# controller.net
KiCad netlist of a schematic drawn in EAGLE
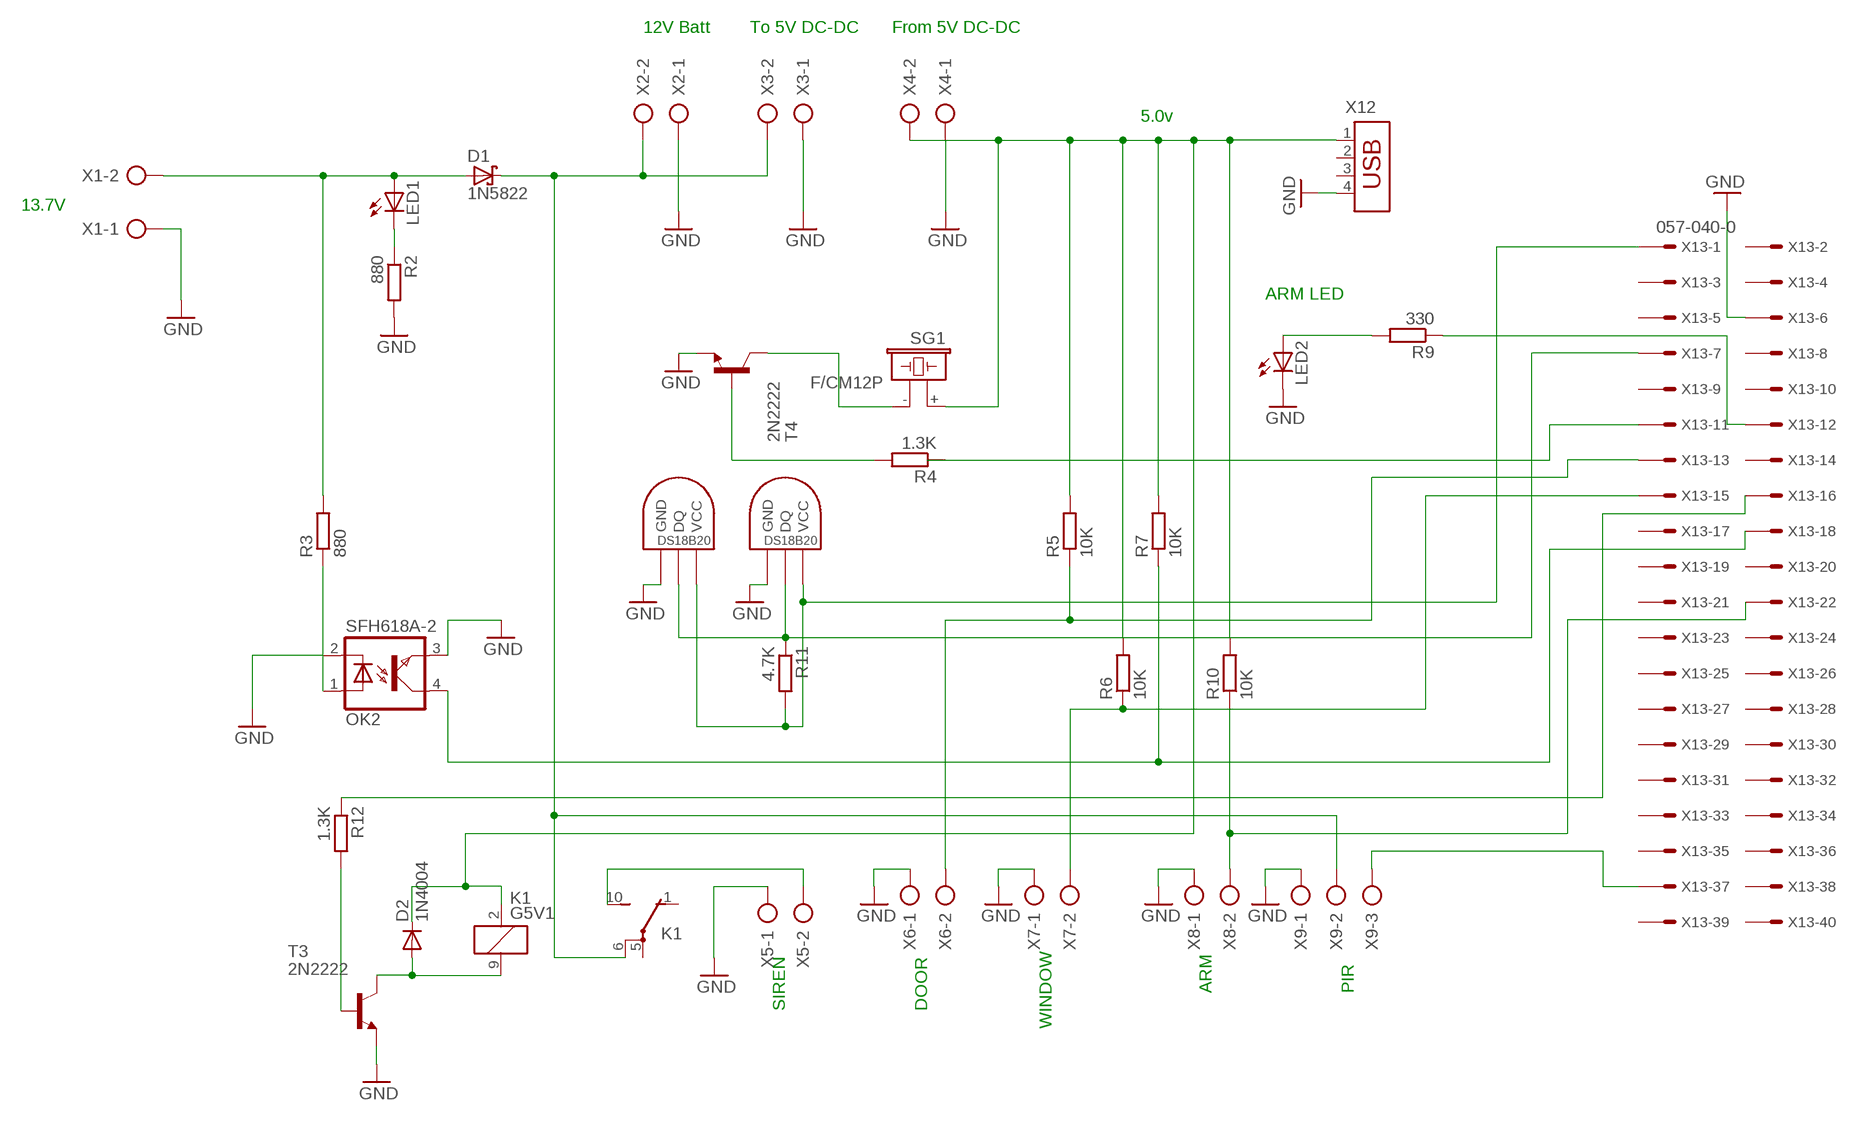
[diagram p0: schematic, sheet 1]

(export (version "E")
  (design (tool "Eeschema 10.0.6"))
  (components
    (comp (ref "D1")
      (value "1N5822")
      (footprint "eagle-import:DO201T15")
      (libsource (lib "eagle-import") (part "SCHOTTKY-DIODEDO201T15"))
    )
    (comp (ref "D2")
      (value "1N4004")
      (footprint "eagle-import:DO41-10")
      (libsource (lib "eagle-import") (part "1N4004"))
    )
    (comp (ref "K1")
      (value "G5V1")
      (footprint "eagle-import:G5V1")
      (fields (field (name "MPN") "G5V-1-DC24"))
      (libsource (lib "eagle-import") (part "G5V1"))
    )
    (comp (ref "LED1")
      (value "LED5MM")
      (footprint "eagle-import:LED5MM")
      (libsource (lib "eagle-import") (part "LED5MM"))
    )
    (comp (ref "LED2")
      (value "LED5MM")
      (footprint "eagle-import:LED5MM")
      (libsource (lib "eagle-import") (part "LED5MM"))
    )
    (comp (ref "OK2")
      (value "SFH618A-2")
      (footprint "eagle-import:DIP4")
      (fields (field (name "MF") "VISHAY/TELEFUNKEN"))
      (libsource (lib "eagle-import") (part "SFH618?A-2"))
    )
    (comp (ref "R2")
      (value "880")
      (footprint "eagle-import:0204_7")
      (libsource (lib "eagle-import") (part "R-EU_0204/7"))
    )
    (comp (ref "R3")
      (value "880")
      (footprint "eagle-import:0204_7")
      (libsource (lib "eagle-import") (part "R-EU_0204/7"))
    )
    (comp (ref "R4")
      (value "1.3K")
      (footprint "eagle-import:0204_7")
      (libsource (lib "eagle-import") (part "R-EU_0204/7"))
    )
    (comp (ref "R5")
      (value "10K")
      (footprint "eagle-import:0204_7")
      (libsource (lib "eagle-import") (part "R-EU_0204/7"))
    )
    (comp (ref "R6")
      (value "10K")
      (footprint "eagle-import:0204_7")
      (libsource (lib "eagle-import") (part "R-EU_0204/7"))
    )
    (comp (ref "R7")
      (value "10K")
      (footprint "eagle-import:0204_7")
      (libsource (lib "eagle-import") (part "R-EU_0204/7"))
    )
    (comp (ref "R9")
      (value "330")
      (footprint "eagle-import:0204_7")
      (libsource (lib "eagle-import") (part "R-EU_0204/7"))
    )
    (comp (ref "R10")
      (value "10K")
      (footprint "eagle-import:0204_7")
      (libsource (lib "eagle-import") (part "R-EU_0204/7"))
    )
    (comp (ref "R11")
      (value "4.7K")
      (footprint "eagle-import:0204_7")
      (libsource (lib "eagle-import") (part "R-EU_0204/7"))
    )
    (comp (ref "R12")
      (value "1.3K")
      (footprint "eagle-import:0204_7")
      (libsource (lib "eagle-import") (part "R-EU_0204/7"))
    )
    (comp (ref "SG1")
      (value "F/CM12P")
      (footprint "eagle-import:F_CM12P")
      (libsource (lib "eagle-import") (part "F/CM12P"))
    )
    (comp (ref "T3")
      (value "2N2222")
      (footprint "eagle-import:TO92-EBC")
      (libsource (lib "eagle-import") (part "-NPN-TO92-EBC2N2222"))
    )
    (comp (ref "T4")
      (value "2N2222")
      (footprint "eagle-import:TO92-EBC")
      (libsource (lib "eagle-import") (part "-NPN-TO92-EBC2N2222"))
    )
    (comp (ref "U$1")
      (value "DS1820TO92")
      (footprint "eagle-import:DS1820")
      (libsource (lib "eagle-import") (part "DS1820TO92"))
    )
    (comp (ref "U$2")
      (value "DS1820TO92")
      (footprint "eagle-import:DS1820")
      (libsource (lib "eagle-import") (part "DS1820TO92"))
    )
    (comp (ref "X1")
      (value "AK500/2")
      (footprint "eagle-import:AK500_2")
      (libsource (lib "eagle-import") (part "AK500/2"))
    )
    (comp (ref "X2")
      (value "AK500/2")
      (footprint "eagle-import:AK500_2")
      (libsource (lib "eagle-import") (part "AK500/2"))
    )
    (comp (ref "X3")
      (value "AK500/2")
      (footprint "eagle-import:AK500_2")
      (libsource (lib "eagle-import") (part "AK500/2"))
    )
    (comp (ref "X4")
      (value "AK500/2")
      (footprint "eagle-import:AK500_2")
      (libsource (lib "eagle-import") (part "AK500/2"))
    )
    (comp (ref "X5")
      (value "AK500/2")
      (footprint "eagle-import:AK500_2")
      (libsource (lib "eagle-import") (part "AK500/2"))
    )
    (comp (ref "X6")
      (value "AK500/2")
      (footprint "eagle-import:AK500_2")
      (libsource (lib "eagle-import") (part "AK500/2"))
    )
    (comp (ref "X7")
      (value "AK500/2")
      (footprint "eagle-import:AK500_2")
      (libsource (lib "eagle-import") (part "AK500/2"))
    )
    (comp (ref "X8")
      (value "AK500/2")
      (footprint "eagle-import:AK500_2")
      (libsource (lib "eagle-import") (part "AK500/2"))
    )
    (comp (ref "X9")
      (value "AK500/3-H")
      (footprint "eagle-import:AK500_3-H")
      (libsource (lib "eagle-import") (part "AK500/3-H"))
    )
    (comp (ref "X12")
      (value "USB-787616")
      (footprint "eagle-import:USB")
      (libsource (lib "eagle-import") (part "USB-787616"))
    )
    (comp (ref "X13")
      (value "057-040-0")
      (footprint "eagle-import:057-040-0")
      (libsource (lib "eagle-import") (part "057-040-0"))
    )
  )
  (nets
    (net (code "1") (name "GND") (class "Default")
      (node (ref "LED2") (pin "K") (pinfunction "C_K") (pintype "passive"))
      (node (ref "OK2") (pin "2") (pinfunction "C_2") (pintype "passive"))
      (node (ref "OK2") (pin "3") (pinfunction "EMIT_3") (pintype "passive"))
      (node (ref "R2") (pin "2") (pinfunction "2_2") (pintype "passive"))
      (node (ref "T3") (pin "E") (pinfunction "E_E") (pintype "passive"))
      (node (ref "T4") (pin "E") (pinfunction "E_E") (pintype "passive"))
      (node (ref "U$1") (pin "GND") (pinfunction "GND_GND") (pintype "power_in"))
      (node (ref "U$2") (pin "GND") (pinfunction "GND_GND") (pintype "power_in"))
      (node (ref "X1") (pin "1") (pinfunction "KL_1") (pintype "passive"))
      (node (ref "X12") (pin "4") (pinfunction "4_4") (pintype "passive"))
      (node (ref "X13") (pin "6") (pinfunction "S_6") (pintype "passive"))
      (node (ref "X2") (pin "1") (pinfunction "KL_1") (pintype "passive"))
      (node (ref "X3") (pin "1") (pinfunction "KL_1") (pintype "passive"))
      (node (ref "X4") (pin "1") (pinfunction "KL_1") (pintype "passive"))
      (node (ref "X5") (pin "1") (pinfunction "KL_1") (pintype "passive"))
      (node (ref "X6") (pin "1") (pinfunction "KL_1") (pintype "passive"))
      (node (ref "X7") (pin "1") (pinfunction "KL_1") (pintype "passive"))
      (node (ref "X8") (pin "1") (pinfunction "KL_1") (pintype "passive"))
      (node (ref "X9") (pin "1") (pinfunction "KL_1") (pintype "passive"))
    )
    (net (code "2") (name "Net-(K1A-1)") (class "Default")
      (node (ref "D2") (pin "C") (pinfunction "C_C") (pintype "passive"))
      (node (ref "K1") (pin "2") (pinfunction "1_2") (pintype "passive"))
      (node (ref "R10") (pin "2") (pinfunction "2_2") (pintype "passive"))
      (node (ref "R5") (pin "2") (pinfunction "2_2") (pintype "passive"))
      (node (ref "R6") (pin "2") (pinfunction "2_2") (pintype "passive"))
      (node (ref "R7") (pin "2") (pinfunction "2_2") (pintype "passive"))
      (node (ref "SG1") (pin "+") (pinfunction "1_+") (pintype "passive"))
      (node (ref "X12") (pin "1") (pinfunction "1_1") (pintype "passive"))
      (node (ref "X4") (pin "2") (pinfunction "KL_2") (pintype "passive"))
    )
    (net (code "3") (name "Net-(K1A-2)") (class "Default")
      (node (ref "D2") (pin "A") (pinfunction "A_A") (pintype "passive"))
      (node (ref "K1") (pin "9") (pinfunction "2_9") (pintype "passive"))
      (node (ref "T3") (pin "C") (pinfunction "C_C") (pintype "passive"))
    )
    (net (code "4") (name "Net-(K1B-S)") (class "Default")
      (node (ref "K1") (pin "10") (pinfunction "S_10") (pintype "passive"))
      (node (ref "X5") (pin "2") (pinfunction "KL_2") (pintype "passive"))
    )
    (net (code "5") (name "Net-(LED1-C)") (class "Default")
      (node (ref "LED1") (pin "K") (pinfunction "C_K") (pintype "passive"))
      (node (ref "R2") (pin "1") (pinfunction "1_1") (pintype "passive"))
    )
    (net (code "6") (name "Net-(LED2-PadA)") (class "Default")
      (node (ref "LED2") (pin "A") (pinfunction "A_A") (pintype "passive"))
      (node (ref "R9") (pin "2") (pinfunction "2_2") (pintype "passive"))
    )
    (net (code "7") (name "Net-(OK2-A)") (class "Default")
      (node (ref "OK2") (pin "1") (pinfunction "A_1") (pintype "passive"))
      (node (ref "R3") (pin "1") (pinfunction "1_1") (pintype "passive"))
    )
    (net (code "8") (name "Net-(OK2-COL)") (class "Default")
      (node (ref "OK2") (pin "4") (pinfunction "COL_4") (pintype "passive"))
      (node (ref "R7") (pin "1") (pinfunction "1_1") (pintype "passive"))
      (node (ref "X13") (pin "18") (pinfunction "S_18") (pintype "passive"))
    )
    (net (code "9") (name "Net-(R4-Pad2)") (class "Default")
      (node (ref "R4") (pin "2") (pinfunction "2_2") (pintype "passive"))
      (node (ref "T4") (pin "B") (pinfunction "B_B") (pintype "passive"))
    )
    (net (code "10") (name "Net-(R12-Pad2)") (class "Default")
      (node (ref "R12") (pin "2") (pinfunction "2_2") (pintype "passive"))
      (node (ref "T3") (pin "B") (pinfunction "B_B") (pintype "passive"))
    )
    (net (code "11") (name "Net-(SG1-2)") (class "Default")
      (node (ref "SG1") (pin "-") (pinfunction "2_-") (pintype "passive"))
      (node (ref "T4") (pin "C") (pinfunction "C_C") (pintype "passive"))
    )
    (net (code "12") (name "Net-(U$1-VCC)") (class "Default")
      (node (ref "R11") (pin "2") (pinfunction "2_2") (pintype "passive"))
      (node (ref "U$1") (pin "VDD") (pinfunction "VCC_VDD") (pintype "power_in"))
      (node (ref "U$2") (pin "VDD") (pinfunction "VCC_VDD") (pintype "power_in"))
      (node (ref "X13") (pin "1") (pinfunction "S_1") (pintype "passive"))
    )
    (net (code "13") (name "Net-(X1B-KL)") (class "Default")
      (node (ref "D1") (pin "A") (pinfunction "A_A") (pintype "passive"))
      (node (ref "LED1") (pin "A") (pinfunction "A_A") (pintype "passive"))
      (node (ref "R3") (pin "2") (pinfunction "2_2") (pintype "passive"))
      (node (ref "X1") (pin "2") (pinfunction "KL_2") (pintype "passive"))
    )
    (net (code "14") (name "Net-(X2B-KL)") (class "Default")
      (node (ref "D1") (pin "C") (pinfunction "C_C") (pintype "passive"))
      (node (ref "K1") (pin "6") (pinfunction "P_6") (pintype "passive"))
      (node (ref "X2") (pin "2") (pinfunction "KL_2") (pintype "passive"))
      (node (ref "X3") (pin "2") (pinfunction "KL_2") (pintype "passive"))
      (node (ref "X9") (pin "2") (pinfunction "KL_2") (pintype "passive"))
    )
    (net (code "15") (name "Net-(X13AE-S)") (class "Default")
      (node (ref "X13") (pin "37") (pinfunction "S_37") (pintype "passive"))
      (node (ref "X9") (pin "3") (pinfunction "KL_3") (pintype "passive"))
    )
    (net (code "16") (name "Net-(X13AL-S)") (class "Default")
      (node (ref "R11") (pin "1") (pinfunction "1_1") (pintype "passive"))
      (node (ref "U$1") (pin "DQ") (pinfunction "DQ_DQ") (pintype "bidirectional"))
      (node (ref "U$2") (pin "DQ") (pinfunction "DQ_DQ") (pintype "bidirectional"))
      (node (ref "X13") (pin "7") (pinfunction "S_7") (pintype "passive"))
    )
    (net (code "17") (name "Net-(X13C-S)") (class "Default")
      (node (ref "R4") (pin "1") (pinfunction "1_1") (pintype "passive"))
      (node (ref "X13") (pin "11") (pinfunction "S_11") (pintype "passive"))
    )
    (net (code "18") (name "Net-(X13D-S)") (class "Default")
      (node (ref "R9") (pin "1") (pinfunction "1_1") (pintype "passive"))
      (node (ref "X13") (pin "12") (pinfunction "S_12") (pintype "passive"))
    )
    (net (code "19") (name "Net-(X13E-S)") (class "Default")
      (node (ref "R5") (pin "1") (pinfunction "1_1") (pintype "passive"))
      (node (ref "X13") (pin "13") (pinfunction "S_13") (pintype "passive"))
      (node (ref "X6") (pin "2") (pinfunction "KL_2") (pintype "passive"))
    )
    (net (code "20") (name "Net-(X13G-S)") (class "Default")
      (node (ref "R6") (pin "1") (pinfunction "1_1") (pintype "passive"))
      (node (ref "X13") (pin "15") (pinfunction "S_15") (pintype "passive"))
      (node (ref "X7") (pin "2") (pinfunction "KL_2") (pintype "passive"))
    )
    (net (code "21") (name "Net-(X13H-S)") (class "Default")
      (node (ref "R12") (pin "1") (pinfunction "1_1") (pintype "passive"))
      (node (ref "X13") (pin "16") (pinfunction "S_16") (pintype "passive"))
    )
    (net (code "22") (name "Net-(X13O-S)") (class "Default")
      (node (ref "R10") (pin "1") (pinfunction "1_1") (pintype "passive"))
      (node (ref "X13") (pin "22") (pinfunction "S_22") (pintype "passive"))
      (node (ref "X8") (pin "2") (pinfunction "KL_2") (pintype "passive"))
    )
    (net (code "23") (name "unconnected-(K1B-O-Pad1)") (class "Default")
      (node (ref "K1") (pin "1") (pinfunction "O_1") (pintype "passive"))
    )
    (net (code "24") (name "unconnected-(K1B-P-Pad5)") (class "Default")
      (node (ref "K1") (pin "5") (pinfunction "P_5") (pintype "passive"))
    )
    (net (code "25") (name "unconnected-(X12-Pad2)") (class "Default")
      (node (ref "X12") (pin "2") (pinfunction "2_2") (pintype "passive"))
    )
    (net (code "26") (name "unconnected-(X12-Pad3)") (class "Default")
      (node (ref "X12") (pin "3") (pinfunction "3_3") (pintype "passive"))
    )
    (net (code "27") (name "unconnected-(X13AA-S-Pad33)") (class "Default")
      (node (ref "X13") (pin "33") (pinfunction "S_33") (pintype "passive"))
    )
    (net (code "28") (name "unconnected-(X13AB-S-Pad34)") (class "Default")
      (node (ref "X13") (pin "34") (pinfunction "S_34") (pintype "passive"))
    )
    (net (code "29") (name "unconnected-(X13AC-S-Pad35)") (class "Default")
      (node (ref "X13") (pin "35") (pinfunction "S_35") (pintype "passive"))
    )
    (net (code "30") (name "unconnected-(X13AD-S-Pad36)") (class "Default")
      (node (ref "X13") (pin "36") (pinfunction "S_36") (pintype "passive"))
    )
    (net (code "31") (name "unconnected-(X13AF-S-Pad38)") (class "Default")
      (node (ref "X13") (pin "38") (pinfunction "S_38") (pintype "passive"))
    )
    (net (code "32") (name "unconnected-(X13AG-S-Pad39)") (class "Default")
      (node (ref "X13") (pin "39") (pinfunction "S_39") (pintype "passive"))
    )
    (net (code "33") (name "unconnected-(X13AH-S-Pad4)") (class "Default")
      (node (ref "X13") (pin "4") (pinfunction "S_4") (pintype "passive"))
    )
    (net (code "34") (name "unconnected-(X13AI-S-Pad40)") (class "Default")
      (node (ref "X13") (pin "40") (pinfunction "S_40") (pintype "passive"))
    )
    (net (code "35") (name "unconnected-(X13AJ-S-Pad5)") (class "Default")
      (node (ref "X13") (pin "5") (pinfunction "S_5") (pintype "passive"))
    )
    (net (code "36") (name "unconnected-(X13AM-S-Pad8)") (class "Default")
      (node (ref "X13") (pin "8") (pinfunction "S_8") (pintype "passive"))
    )
    (net (code "37") (name "unconnected-(X13AN-S-Pad9)") (class "Default")
      (node (ref "X13") (pin "9") (pinfunction "S_9") (pintype "passive"))
    )
    (net (code "38") (name "unconnected-(X13B-S-Pad10)") (class "Default")
      (node (ref "X13") (pin "10") (pinfunction "S_10") (pintype "passive"))
    )
    (net (code "39") (name "unconnected-(X13F-S-Pad14)") (class "Default")
      (node (ref "X13") (pin "14") (pinfunction "S_14") (pintype "passive"))
    )
    (net (code "40") (name "unconnected-(X13I-S-Pad17)") (class "Default")
      (node (ref "X13") (pin "17") (pinfunction "S_17") (pintype "passive"))
    )
    (net (code "41") (name "unconnected-(X13K-S-Pad19)") (class "Default")
      (node (ref "X13") (pin "19") (pinfunction "S_19") (pintype "passive"))
    )
    (net (code "42") (name "unconnected-(X13L-S-Pad2)") (class "Default")
      (node (ref "X13") (pin "2") (pinfunction "S_2") (pintype "passive"))
    )
    (net (code "43") (name "unconnected-(X13M-S-Pad20)") (class "Default")
      (node (ref "X13") (pin "20") (pinfunction "S_20") (pintype "passive"))
    )
    (net (code "44") (name "unconnected-(X13N-S-Pad21)") (class "Default")
      (node (ref "X13") (pin "21") (pinfunction "S_21") (pintype "passive"))
    )
    (net (code "45") (name "unconnected-(X13P-S-Pad23)") (class "Default")
      (node (ref "X13") (pin "23") (pinfunction "S_23") (pintype "passive"))
    )
    (net (code "46") (name "unconnected-(X13Q-S-Pad24)") (class "Default")
      (node (ref "X13") (pin "24") (pinfunction "S_24") (pintype "passive"))
    )
    (net (code "47") (name "unconnected-(X13R-S-Pad25)") (class "Default")
      (node (ref "X13") (pin "25") (pinfunction "S_25") (pintype "passive"))
    )
    (net (code "48") (name "unconnected-(X13S-S-Pad26)") (class "Default")
      (node (ref "X13") (pin "26") (pinfunction "S_26") (pintype "passive"))
    )
    (net (code "49") (name "unconnected-(X13T-S-Pad27)") (class "Default")
      (node (ref "X13") (pin "27") (pinfunction "S_27") (pintype "passive"))
    )
    (net (code "50") (name "unconnected-(X13U-S-Pad28)") (class "Default")
      (node (ref "X13") (pin "28") (pinfunction "S_28") (pintype "passive"))
    )
    (net (code "51") (name "unconnected-(X13V-S-Pad29)") (class "Default")
      (node (ref "X13") (pin "29") (pinfunction "S_29") (pintype "passive"))
    )
    (net (code "52") (name "unconnected-(X13W-S-Pad3)") (class "Default")
      (node (ref "X13") (pin "3") (pinfunction "S_3") (pintype "passive"))
    )
    (net (code "53") (name "unconnected-(X13X-S-Pad30)") (class "Default")
      (node (ref "X13") (pin "30") (pinfunction "S_30") (pintype "passive"))
    )
    (net (code "54") (name "unconnected-(X13Y-S-Pad31)") (class "Default")
      (node (ref "X13") (pin "31") (pinfunction "S_31") (pintype "passive"))
    )
    (net (code "55") (name "unconnected-(X13Z-S-Pad32)") (class "Default")
      (node (ref "X13") (pin "32") (pinfunction "S_32") (pintype "passive"))
    )
  )
)
